# SoftCore_SA_P5.net
KiCad netlist of a schematic drawn in Altium Designer
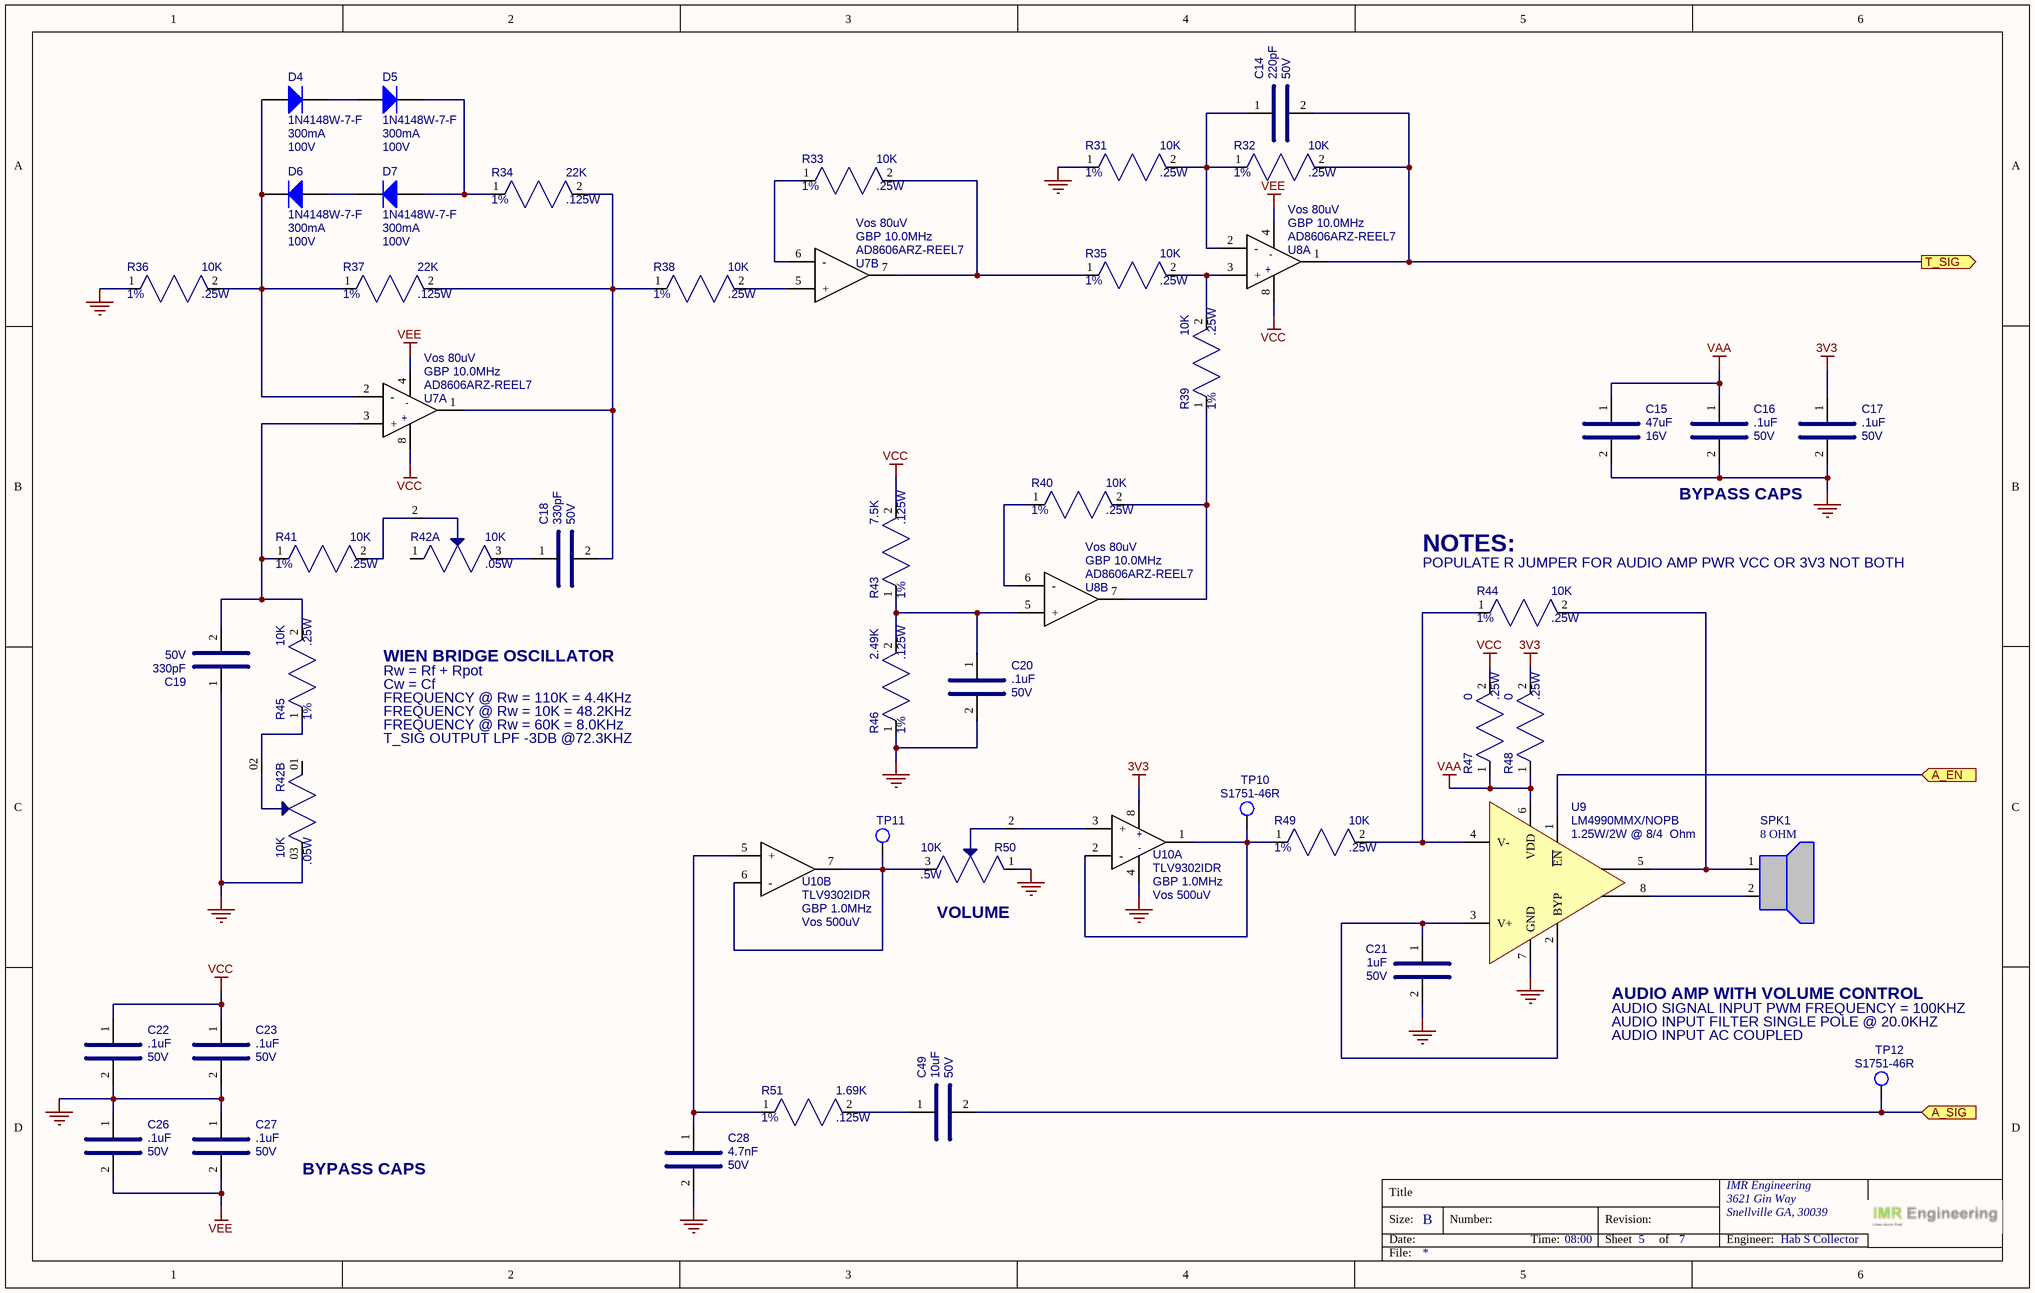
[diagram p0: SoftCore_SA_P5.SchDoc]

(export (version "E")
  (design (tool "Eeschema 10.0.6"))
  (components
    (comp (ref "C14")
      (value "220pF")
      (footprint "CAP_0805")
      (description "CAP CER 220PF 50V COG/NP0 0805")
      (fields (field (name "MFG") "Yageo") (field (name "TOLERANCE") "5%") (field (name "VOLTAGE") "50V"))
      (libsource (lib "IMR_LIB_SCH_R2") (part "CAP_SMD_220PF_50V_0805"))
    )
    (comp (ref "C15")
      (value "47uF")
      (footprint "CAP_1210")
      (description "CAP CER 47UF 50V X5R 1210")
      (fields
        (field (name "MFG") "Murata Electronics")
        (field (name "VOLTAGE") "16V")
        (field (name "Comment") "GRM32ER60J476ME20L")
      )
      (libsource (lib "IMR_LIB_SCH_R2") (part "CAP_SMD_47UF_16V_1210"))
    )
    (comp (ref "C16")
      (value ".1uF")
      (footprint "CAP_0805")
      (description "CAP CER 0.1UF 50V X7R 0805")
      (fields
        (field (name "MFG") "KYOCERA AVX")
        (field (name "VOLTAGE") "50V")
        (field (name "Comment") "KGM21NR71H104KT")
      )
      (libsource (lib "IMR_LIB_SCH_R2") (part "CAP_SMD_0.1UF_50V_0805"))
    )
    (comp (ref "C17")
      (value ".1uF")
      (footprint "CAP_0805")
      (description "CAP CER 0.1UF 50V X7R 0805")
      (fields
        (field (name "MFG") "KYOCERA AVX")
        (field (name "VOLTAGE") "50V")
        (field (name "Comment") "KGM21NR71H104KT")
      )
      (libsource (lib "IMR_LIB_SCH_R2") (part "CAP_SMD_0.1UF_50V_0805"))
    )
    (comp (ref "C18")
      (value "330pF")
      (footprint "CAP_0805")
      (description "CAP CER 3300PF 50V COG/NP0 0805")
      (fields (field (name "MFG") "Yageo") (field (name "TOLERANCE") "5%") (field (name "VOLTAGE") "50V"))
      (libsource (lib "IMR_LIB_SCH_R2") (part "CAP_SMD_330PF_50V_0805"))
    )
    (comp (ref "C19")
      (value "330pF")
      (footprint "CAP_0805")
      (description "CAP CER 3300PF 50V COG/NP0 0805")
      (fields (field (name "MFG") "Yageo") (field (name "TOLERANCE") "5%") (field (name "VOLTAGE") "50V"))
      (libsource (lib "IMR_LIB_SCH_R2") (part "CAP_SMD_330PF_50V_0805"))
    )
    (comp (ref "C20")
      (value ".1uF")
      (footprint "CAP_0805")
      (description "CAP CER 0.1UF 50V X7R 0805")
      (fields
        (field (name "MFG") "KYOCERA AVX")
        (field (name "VOLTAGE") "50V")
        (field (name "Comment") "KGM21NR71H104KT")
      )
      (libsource (lib "IMR_LIB_SCH_R2") (part "CAP_SMD_0.1UF_50V_0805"))
    )
    (comp (ref "C21")
      (value "1uF")
      (footprint "CAP_0805")
      (description "CAP CER 1UF 50V X7R 0805")
      (fields
        (field (name "MFG") "KYOCERA AVX")
        (field (name "VOLTAGE") "50V")
        (field (name "Comment") "08055C105K4T2A")
      )
      (libsource (lib "IMR_LIB_SCH_R2") (part "CAP_SMD_1UF_50V_0805"))
    )
    (comp (ref "C22")
      (value ".1uF")
      (footprint "CAP_0805")
      (description "CAP CER 0.1UF 50V X7R 0805")
      (fields
        (field (name "MFG") "KYOCERA AVX")
        (field (name "VOLTAGE") "50V")
        (field (name "Comment") "KGM21NR71H104KT")
      )
      (libsource (lib "IMR_LIB_SCH_R2") (part "CAP_SMD_0.1UF_50V_0805"))
    )
    (comp (ref "C23")
      (value ".1uF")
      (footprint "CAP_0805")
      (description "CAP CER 0.1UF 50V X7R 0805")
      (fields
        (field (name "MFG") "KYOCERA AVX")
        (field (name "VOLTAGE") "50V")
        (field (name "Comment") "KGM21NR71H104KT")
      )
      (libsource (lib "IMR_LIB_SCH_R2") (part "CAP_SMD_0.1UF_50V_0805"))
    )
    (comp (ref "C26")
      (value ".1uF")
      (footprint "CAP_0805")
      (description "CAP CER 0.1UF 50V X7R 0805")
      (fields
        (field (name "MFG") "KYOCERA AVX")
        (field (name "VOLTAGE") "50V")
        (field (name "Comment") "KGM21NR71H104KT")
      )
      (libsource (lib "IMR_LIB_SCH_R2") (part "CAP_SMD_0.1UF_50V_0805"))
    )
    (comp (ref "C27")
      (value ".1uF")
      (footprint "CAP_0805")
      (description "CAP CER 0.1UF 50V X7R 0805")
      (fields
        (field (name "MFG") "KYOCERA AVX")
        (field (name "VOLTAGE") "50V")
        (field (name "Comment") "KGM21NR71H104KT")
      )
      (libsource (lib "IMR_LIB_SCH_R2") (part "CAP_SMD_0.1UF_50V_0805"))
    )
    (comp (ref "C28")
      (value "4.7nF")
      (footprint "CAP_0805")
      (description "CAP CER 4.7NF 50V X7R 0805")
      (fields
        (field (name "MFG") "KEMET")
        (field (name "VOLTAGE") "50V")
        (field (name "Comment") "C0805C472K5RACAUTO")
      )
      (libsource (lib "IMR_LIB_SCH_R2") (part "CAP_SMD_4.7NF_50V_0805"))
    )
    (comp (ref "C49")
      (value "10uF")
      (footprint "CAP_0805")
      (description "CAP CER 10UF 50V X5R 0805")
      (fields
        (field (name "MFG") "Murata Electronics")
        (field (name "VOLTAGE") "50V")
        (field (name "Comment") "GRM21BR61H106KE43L")
      )
      (libsource (lib "IMR_LIB_SCH_R2") (part "CAP_SMD_10UF_50V_0805"))
    )
    (comp (ref "D4")
      (value "100V")
      (footprint "SOD123")
      (description "RELAY REED SPDT 250MA 5V")
      (fields
        (field (name "MFG") "Diodes Inc")
        (field (name "MFG_PN") "1N4148W-7-F")
        (field (name "CURRENT") "300mA")
        (field (name "Comment") "1N4148W-7-F")
      )
      (libsource (lib "IMR_LIB_SCH_R2") (part "DIODE_1N4148W-7-F"))
    )
    (comp (ref "D5")
      (value "100V")
      (footprint "SOD123")
      (description "RELAY REED SPDT 250MA 5V")
      (fields
        (field (name "MFG") "Diodes Inc")
        (field (name "MFG_PN") "1N4148W-7-F")
        (field (name "CURRENT") "300mA")
        (field (name "Comment") "1N4148W-7-F")
      )
      (libsource (lib "IMR_LIB_SCH_R2") (part "DIODE_1N4148W-7-F"))
    )
    (comp (ref "D6")
      (value "100V")
      (footprint "SOD123")
      (description "RELAY REED SPDT 250MA 5V")
      (fields
        (field (name "MFG") "Diodes Inc")
        (field (name "MFG_PN") "1N4148W-7-F")
        (field (name "CURRENT") "300mA")
        (field (name "Comment") "1N4148W-7-F")
      )
      (libsource (lib "IMR_LIB_SCH_R2") (part "DIODE_1N4148W-7-F"))
    )
    (comp (ref "D7")
      (value "100V")
      (footprint "SOD123")
      (description "RELAY REED SPDT 250MA 5V")
      (fields
        (field (name "MFG") "Diodes Inc")
        (field (name "MFG_PN") "1N4148W-7-F")
        (field (name "CURRENT") "300mA")
        (field (name "Comment") "1N4148W-7-F")
      )
      (libsource (lib "IMR_LIB_SCH_R2") (part "DIODE_1N4148W-7-F"))
    )
    (comp (ref "R31")
      (value "10K")
      (footprint "RES_0805")
      (description "RES SMD 10K OHM 1% 1/4W 0805")
      (fields
        (field (name "MFG") "Yageo")
        (field (name "POWER") ".25W")
        (field (name "TOLERANCE") "1%")
        (field (name "Comment") "RC0805FR-7W10KL")
      )
      (libsource (lib "IMR_LIB_SCH_R2") (part "RES_SMD_10K_0805_1/4W_1%"))
    )
    (comp (ref "R32")
      (value "10K")
      (footprint "RES_0805")
      (description "RES SMD 10K OHM 1% 1/4W 0805")
      (fields
        (field (name "MFG") "Yageo")
        (field (name "POWER") ".25W")
        (field (name "TOLERANCE") "1%")
        (field (name "Comment") "RC0805FR-7W10KL")
      )
      (libsource (lib "IMR_LIB_SCH_R2") (part "RES_SMD_10K_0805_1/4W_1%"))
    )
    (comp (ref "R33")
      (value "10K")
      (footprint "RES_0805")
      (description "RES SMD 10K OHM 1% 1/4W 0805")
      (fields
        (field (name "MFG") "Yageo")
        (field (name "POWER") ".25W")
        (field (name "TOLERANCE") "1%")
        (field (name "Comment") "RC0805FR-7W10KL")
      )
      (libsource (lib "IMR_LIB_SCH_R2") (part "RES_SMD_10K_0805_1/4W_1%"))
    )
    (comp (ref "R34")
      (value "22K")
      (footprint "RES_0805")
      (description "RES SMD 22K OHM 1% 1/8W 0805")
      (fields
        (field (name "MFG") "Yageo")
        (field (name "POWER") ".125W")
        (field (name "TOLERANCE") "1%")
        (field (name "Comment") "RC0805FR-0722KL")
      )
      (libsource (lib "IMR_LIB_SCH_R2") (part "RES_SMD_22K_0805_1/8W_1%"))
    )
    (comp (ref "R35")
      (value "10K")
      (footprint "RES_0805")
      (description "RES SMD 10K OHM 1% 1/4W 0805")
      (fields
        (field (name "MFG") "Yageo")
        (field (name "POWER") ".25W")
        (field (name "TOLERANCE") "1%")
        (field (name "Comment") "RC0805FR-7W10KL")
      )
      (libsource (lib "IMR_LIB_SCH_R2") (part "RES_SMD_10K_0805_1/4W_1%"))
    )
    (comp (ref "R36")
      (value "10K")
      (footprint "RES_0805")
      (description "RES SMD 10K OHM 1% 1/4W 0805")
      (fields
        (field (name "MFG") "Yageo")
        (field (name "POWER") ".25W")
        (field (name "TOLERANCE") "1%")
        (field (name "Comment") "RC0805FR-7W10KL")
      )
      (libsource (lib "IMR_LIB_SCH_R2") (part "RES_SMD_10K_0805_1/4W_1%"))
    )
    (comp (ref "R37")
      (value "22K")
      (footprint "RES_0805")
      (description "RES SMD 22K OHM 1% 1/8W 0805")
      (fields
        (field (name "MFG") "Yageo")
        (field (name "POWER") ".125W")
        (field (name "TOLERANCE") "1%")
        (field (name "Comment") "RC0805FR-0722KL")
      )
      (libsource (lib "IMR_LIB_SCH_R2") (part "RES_SMD_22K_0805_1/8W_1%"))
    )
    (comp (ref "R38")
      (value "10K")
      (footprint "RES_0805")
      (description "RES SMD 10K OHM 1% 1/4W 0805")
      (fields
        (field (name "MFG") "Yageo")
        (field (name "POWER") ".25W")
        (field (name "TOLERANCE") "1%")
        (field (name "Comment") "RC0805FR-7W10KL")
      )
      (libsource (lib "IMR_LIB_SCH_R2") (part "RES_SMD_10K_0805_1/4W_1%"))
    )
    (comp (ref "R39")
      (value "10K")
      (footprint "RES_0805")
      (description "RES SMD 10K OHM 1% 1/4W 0805")
      (fields
        (field (name "MFG") "Yageo")
        (field (name "POWER") ".25W")
        (field (name "TOLERANCE") "1%")
        (field (name "Comment") "RC0805FR-7W10KL")
      )
      (libsource (lib "IMR_LIB_SCH_R2") (part "RES_SMD_10K_0805_1/4W_1%"))
    )
    (comp (ref "R40")
      (value "10K")
      (footprint "RES_0805")
      (description "RES SMD 10K OHM 1% 1/4W 0805")
      (fields
        (field (name "MFG") "Yageo")
        (field (name "POWER") ".25W")
        (field (name "TOLERANCE") "1%")
        (field (name "Comment") "RC0805FR-7W10KL")
      )
      (libsource (lib "IMR_LIB_SCH_R2") (part "RES_SMD_10K_0805_1/4W_1%"))
    )
    (comp (ref "R41")
      (value "10K")
      (footprint "RES_0805")
      (description "RES SMD 10K OHM 1% 1/4W 0805")
      (fields
        (field (name "MFG") "Yageo")
        (field (name "POWER") ".25W")
        (field (name "TOLERANCE") "1%")
        (field (name "Comment") "RC0805FR-7W10KL")
      )
      (libsource (lib "IMR_LIB_SCH_R2") (part "RES_SMD_10K_0805_1/4W_1%"))
    )
    (comp (ref "R42")
      (value "10K")
      (footprint "PRS12R-4")
      (description "POT 10K OHM 1/20W LINEAR - 2X GANG")
      (fields
        (field (name "MFG") "Bourns Inc.")
        (field (name "POWER") ".05W")
        (field (name "Comment") "PRS12R-4115K-103B1")
      )
      (libsource (lib "IMR_LIB_SCH_R2") (part "RES_POT_10K_2XGANG_LINEAR"))
    )
    (comp (ref "R43")
      (value "7.5K")
      (footprint "RES_0805")
      (description "RES SMD 7.5K OHM 1% 1/8W 0805")
      (fields
        (field (name "MFG") "Yageo")
        (field (name "POWER") ".125W")
        (field (name "TOLERANCE") "1%")
        (field (name "Comment") "RC0805FR-077K5L")
      )
      (libsource (lib "IMR_LIB_SCH_R2") (part "RES_SMD_7.5K_0805_1/8W_1%"))
    )
    (comp (ref "R44")
      (value "10K")
      (footprint "RES_0805")
      (description "RES SMD 10K OHM 1% 1/4W 0805")
      (fields
        (field (name "MFG") "Yageo")
        (field (name "POWER") ".25W")
        (field (name "TOLERANCE") "1%")
        (field (name "Comment") "RC0805FR-7W10KL")
      )
      (libsource (lib "IMR_LIB_SCH_R2") (part "RES_SMD_10K_0805_1/4W_1%"))
    )
    (comp (ref "R45")
      (value "10K")
      (footprint "RES_0805")
      (description "RES SMD 10K OHM 1% 1/4W 0805")
      (fields
        (field (name "MFG") "Yageo")
        (field (name "POWER") ".25W")
        (field (name "TOLERANCE") "1%")
        (field (name "Comment") "RC0805FR-7W10KL")
      )
      (libsource (lib "IMR_LIB_SCH_R2") (part "RES_SMD_10K_0805_1/4W_1%"))
    )
    (comp (ref "R46")
      (value "2.49K")
      (footprint "RES_0805")
      (description "RES SMD 2.49K OHM 1% 1/8W 0805")
      (fields
        (field (name "MFG") "Yageo")
        (field (name "POWER") ".125W")
        (field (name "TOLERANCE") "1%")
        (field (name "Comment") "RC0805FR-132K49L")
      )
      (libsource (lib "IMR_LIB_SCH_R2") (part "RES_SMD_2.49K_0805_1/8W_1%"))
    )
    (comp (ref "R47")
      (value "0")
      (footprint "RES_0805")
      (description "RES SMD 0 OHM 1% 1/8W 0805")
      (fields (field (name "MFG") "Yageo") (field (name "TOLERANCE") "1%") (field (name "POWER") ".25W"))
      (libsource (lib "IMR_LIB_SCH_R2") (part "RES_SMD_0_0805_1/8W_1%"))
    )
    (comp (ref "R48")
      (value "0")
      (footprint "RES_0805")
      (description "RES SMD 0 OHM 1% 1/8W 0805")
      (fields (field (name "MFG") "Yageo") (field (name "TOLERANCE") "1%") (field (name "POWER") ".25W"))
      (libsource (lib "IMR_LIB_SCH_R2") (part "RES_SMD_0_0805_1/8W_1%"))
    )
    (comp (ref "R49")
      (value "10K")
      (footprint "RES_0805")
      (description "RES SMD 10K OHM 1% 1/4W 0805")
      (fields
        (field (name "MFG") "Yageo")
        (field (name "POWER") ".25W")
        (field (name "TOLERANCE") "1%")
        (field (name "Comment") "RC0805FR-7W10KL")
      )
      (libsource (lib "IMR_LIB_SCH_R2") (part "RES_SMD_10K_0805_1/4W_1%"))
    )
    (comp (ref "R50")
      (value "10K")
      (footprint "BOURNS_3386F")
      (description "POT 10K OHM 1/20W LINEAR - 1X GANG")
      (fields
        (field (name "MFG") "Bourns Inc.")
        (field (name "POWER") ".5W")
        (field (name "Comment") "3386P-1-103TLF")
      )
      (libsource (lib "IMR_LIB_SCH_R2") (part "RES_POT_10K_1XGANG_LINEAR"))
    )
    (comp (ref "R51")
      (value "1.69K")
      (footprint "RES_0805")
      (description "RES SMD 1.69K OHM 1% 1/8W 0805")
      (fields
        (field (name "MFG") "Yageo")
        (field (name "POWER") ".125W")
        (field (name "TOLERANCE") "1%")
        (field (name "Comment") "RC0805FR-071K69L")
      )
      (libsource (lib "IMR_LIB_SCH_R2") (part "RES_SMD_1.69K_0805_1/8W_1%"))
    )
    (comp (ref "SPK1")
      (value "8 OHM")
      (footprint "HDR_1X2_100MILL")
      (description "CONN SPEAKER HEADER GENERIC VERT 2POS 2.54MM")
      (fields (field (name "MFG") "GENERIC") (field (name "Comment") "TBD"))
      (libsource (lib "IMR_LIB_SCH_R2") (part "CONN_SPKR_HEADER_2P_100MIL"))
    )
    (comp (ref "TP10")
      (value "S1751-46R")
      (footprint "HARWIN_S1751")
      (description "PCB TEST POINT CONNECT")
      (fields (field (name "MFG") "Harwin Inc") (field (name "MFG_PN") "S1751-46R"))
      (libsource (lib "IMR_LIB_SCH_R2") (part "CONN_TEST_POINT_S1751-46R"))
    )
    (comp (ref "TP11")
      (value "~")
      (footprint "TEST_POINT_20MIL_TH")
      (description "TEST POINT TH 20MIL HOLE")
      (libsource (lib "IMR_LIB_SCH_R2") (part "CONN_TEST_POINT_TH_PAD_20MIL"))
    )
    (comp (ref "TP12")
      (value "S1751-46R")
      (footprint "HARWIN_S1751")
      (description "PCB TEST POINT CONNECT")
      (fields (field (name "MFG") "Harwin Inc") (field (name "MFG_PN") "S1751-46R"))
      (libsource (lib "IMR_LIB_SCH_R2") (part "CONN_TEST_POINT_S1751-46R"))
    )
    (comp (ref "U7")
      (value "GBP 10.0MHz")
      (footprint "SOIC-8_54")
      (description "IC OPAMP GP 2 CIRCUIT 8SOIC")
      (fields
        (field (name "MFG") "Analog Devices")
        (field (name "MFG_PN") "AD8606ARZ-REEL7")
        (field (name "VOS") "Vos 80uV")
        (field (name "Comment") "AD8606ARZ-REEL7")
      )
      (libsource (lib "IMR_LIB_SCH_R2") (part "IC_OPAMP_AD8606ARZ-REEL7"))
    )
    (comp (ref "U8")
      (value "GBP 10.0MHz")
      (footprint "SOIC-8_54")
      (description "IC OPAMP GP 2 CIRCUIT 8SOIC")
      (fields
        (field (name "MFG") "Analog Devices")
        (field (name "MFG_PN") "AD8606ARZ-REEL7")
        (field (name "VOS") "Vos 80uV")
        (field (name "Comment") "AD8606ARZ-REEL7")
      )
      (libsource (lib "IMR_LIB_SCH_R2") (part "IC_OPAMP_AD8606ARZ-REEL7"))
    )
    (comp (ref "U9")
      (value "1.25W/2W @ 8/4  Ohm")
      (footprint "SOP65P490X110-8N")
      (description "IC AMP CLASS AB MONO 2W 8VSSOP")
      (fields
        (field (name "MFG") "Texas Instruments")
        (field (name "MFG_PN") "LM4990MMX/NOPB")
        (field (name "Comment") "LM4990MMX/NOPB")
      )
      (libsource (lib "IMR_LIB_SCH_R2") (part "IC_LM4990MMX/NOPB"))
    )
    (comp (ref "U10")
      (value "GBP 1.0MHz")
      (footprint "SOIC-8_49")
      (description "IC OPAMP GP 2 CIRCUIT 8SOIC")
      (fields
        (field (name "MFG") "Texas Instruments")
        (field (name "MFG_PN") "TLV9302IDR")
        (field (name "VOS") "Vos 500uV")
        (field (name "Comment") "TLV9302IDR")
      )
      (libsource (lib "IMR_LIB_SCH_R2") (part "IC_OPAMP_TLV9302IDR"))
    )
  )
  (nets
    (net (code "1") (name "/A_EN") (class "Default")
      (node (ref "U9") (pin "1") (pinfunction "EN_1") (pintype "passive"))
    )
    (net (code "2") (name "/A_SIG") (class "Default")
      (node (ref "C49") (pin "2") (pinfunction "2_2") (pintype "passive"))
      (node (ref "TP12") (pin "1") (pintype "passive"))
    )
    (net (code "3") (name "/T_SIG") (class "Default")
      (node (ref "C14") (pin "2") (pinfunction "2_2") (pintype "passive"))
      (node (ref "R32") (pin "2") (pinfunction "2_2") (pintype "passive"))
      (node (ref "U8") (pin "1") (pintype "passive"))
    )
    (net (code "4") (name "3V3") (class "Default")
      (node (ref "C17") (pin "1") (pinfunction "1_1") (pintype "passive"))
      (node (ref "R48") (pin "2") (pinfunction "2_2") (pintype "passive"))
      (node (ref "U10") (pin "8") (pintype "passive"))
    )
    (net (code "5") (name "GND") (class "Default")
      (node (ref "C15") (pin "2") (pinfunction "2_2") (pintype "passive"))
      (node (ref "C16") (pin "2") (pinfunction "2_2") (pintype "passive"))
      (node (ref "C17") (pin "2") (pinfunction "2_2") (pintype "passive"))
      (node (ref "C19") (pin "1") (pinfunction "1_1") (pintype "passive"))
      (node (ref "C20") (pin "2") (pinfunction "2_2") (pintype "passive"))
      (node (ref "C21") (pin "2") (pinfunction "2_2") (pintype "passive"))
      (node (ref "C22") (pin "2") (pinfunction "2_2") (pintype "passive"))
      (node (ref "C23") (pin "2") (pinfunction "2_2") (pintype "passive"))
      (node (ref "C26") (pin "1") (pinfunction "1_1") (pintype "passive"))
      (node (ref "C27") (pin "1") (pinfunction "1_1") (pintype "passive"))
      (node (ref "C28") (pin "2") (pinfunction "2_2") (pintype "passive"))
      (node (ref "R31") (pin "1") (pinfunction "1_1") (pintype "passive"))
      (node (ref "R36") (pin "1") (pinfunction "1_1") (pintype "passive"))
      (node (ref "R42") (pin "03") (pinfunction "3_03") (pintype "passive"))
      (node (ref "R46") (pin "1") (pinfunction "1_1") (pintype "passive"))
      (node (ref "R50") (pin "1") (pinfunction "1_1") (pintype "passive"))
      (node (ref "U10") (pin "4") (pintype "passive"))
      (node (ref "U9") (pin "7") (pinfunction "GND_7") (pintype "passive"))
    )
    (net (code "6") (name "Net-(C18-Pad1)") (class "Default")
      (node (ref "C18") (pin "1") (pinfunction "1_1") (pintype "passive"))
      (node (ref "R42") (pin "3") (pinfunction "3_3") (pintype "passive"))
    )
    (net (code "7") (name "Net-(C18-Pad2)") (class "Default")
      (node (ref "C18") (pin "2") (pinfunction "2_2") (pintype "passive"))
      (node (ref "R34") (pin "2") (pinfunction "2_2") (pintype "passive"))
      (node (ref "R37") (pin "2") (pinfunction "2_2") (pintype "passive"))
      (node (ref "R38") (pin "1") (pinfunction "1_1") (pintype "passive"))
      (node (ref "U7") (pin "1") (pintype "passive"))
    )
    (net (code "8") (name "Net-(C49-Pad1)") (class "Default")
      (node (ref "C49") (pin "1") (pinfunction "1_1") (pintype "passive"))
      (node (ref "R51") (pin "2") (pinfunction "2_2") (pintype "passive"))
    )
    (net (code "9") (name "Net-(D4-A)") (class "Default")
      (node (ref "D4") (pin "1") (pinfunction "A_1") (pintype "passive"))
      (node (ref "D6") (pin "2") (pinfunction "K_2") (pintype "passive"))
      (node (ref "R36") (pin "2") (pinfunction "2_2") (pintype "passive"))
      (node (ref "R37") (pin "1") (pinfunction "1_1") (pintype "passive"))
      (node (ref "U7") (pin "2") (pinfunction "-_2") (pintype "passive"))
    )
    (net (code "10") (name "Net-(D4-K)") (class "Default")
      (node (ref "D4") (pin "2") (pinfunction "K_2") (pintype "passive"))
      (node (ref "D5") (pin "1") (pinfunction "A_1") (pintype "passive"))
    )
    (net (code "11") (name "Net-(D5-K)") (class "Default")
      (node (ref "D5") (pin "2") (pinfunction "K_2") (pintype "passive"))
      (node (ref "D7") (pin "1") (pinfunction "A_1") (pintype "passive"))
      (node (ref "R34") (pin "1") (pinfunction "1_1") (pintype "passive"))
    )
    (net (code "12") (name "Net-(D6-A)") (class "Default")
      (node (ref "D6") (pin "1") (pinfunction "A_1") (pintype "passive"))
      (node (ref "D7") (pin "2") (pinfunction "K_2") (pintype "passive"))
    )
    (net (code "13") (name "Net-(R33-Pad2)") (class "Default")
      (node (ref "R33") (pin "2") (pinfunction "2_2") (pintype "passive"))
      (node (ref "R35") (pin "1") (pinfunction "1_1") (pintype "passive"))
      (node (ref "U7") (pin "7") (pintype "passive"))
    )
    (net (code "14") (name "Net-(R39-Pad1)") (class "Default")
      (node (ref "R39") (pin "1") (pinfunction "1_1") (pintype "passive"))
      (node (ref "R40") (pin "2") (pinfunction "2_2") (pintype "passive"))
      (node (ref "U8") (pin "7") (pintype "passive"))
    )
    (net (code "15") (name "Net-(R41-Pad2)") (class "Default")
      (node (ref "R41") (pin "2") (pinfunction "2_2") (pintype "passive"))
      (node (ref "R42") (pin "2") (pinfunction "2_2") (pintype "passive"))
    )
    (net (code "16") (name "Net-(R42-Pad02)") (class "Default")
      (node (ref "R42") (pin "02") (pinfunction "02_02") (pintype "passive"))
      (node (ref "R45") (pin "1") (pinfunction "1_1") (pintype "passive"))
    )
    (net (code "17") (name "Net-(U7A-+)") (class "Default")
      (node (ref "C19") (pin "2") (pinfunction "2_2") (pintype "passive"))
      (node (ref "R41") (pin "1") (pinfunction "1_1") (pintype "passive"))
      (node (ref "R45") (pin "2") (pinfunction "2_2") (pintype "passive"))
      (node (ref "U7") (pin "3") (pinfunction "+_3") (pintype "passive"))
    )
    (net (code "18") (name "Net-(U7B-+)") (class "Default")
      (node (ref "R38") (pin "2") (pinfunction "2_2") (pintype "passive"))
      (node (ref "U7") (pin "5") (pinfunction "+_5") (pintype "passive"))
    )
    (net (code "19") (name "Net-(U7B--)") (class "Default")
      (node (ref "R33") (pin "1") (pinfunction "1_1") (pintype "passive"))
      (node (ref "U7") (pin "6") (pinfunction "-_6") (pintype "passive"))
    )
    (net (code "20") (name "Net-(U8A-+)") (class "Default")
      (node (ref "R35") (pin "2") (pinfunction "2_2") (pintype "passive"))
      (node (ref "R39") (pin "2") (pinfunction "2_2") (pintype "passive"))
      (node (ref "U8") (pin "3") (pinfunction "+_3") (pintype "passive"))
    )
    (net (code "21") (name "Net-(U8A--)") (class "Default")
      (node (ref "C14") (pin "1") (pinfunction "1_1") (pintype "passive"))
      (node (ref "R31") (pin "2") (pinfunction "2_2") (pintype "passive"))
      (node (ref "R32") (pin "1") (pinfunction "1_1") (pintype "passive"))
      (node (ref "U8") (pin "2") (pinfunction "-_2") (pintype "passive"))
    )
    (net (code "22") (name "Net-(U8B-+)") (class "Default")
      (node (ref "C20") (pin "1") (pinfunction "1_1") (pintype "passive"))
      (node (ref "R43") (pin "1") (pinfunction "1_1") (pintype "passive"))
      (node (ref "R46") (pin "2") (pinfunction "2_2") (pintype "passive"))
      (node (ref "U8") (pin "5") (pinfunction "+_5") (pintype "passive"))
    )
    (net (code "23") (name "Net-(U8B--)") (class "Default")
      (node (ref "R40") (pin "1") (pinfunction "1_1") (pintype "passive"))
      (node (ref "U8") (pin "6") (pinfunction "-_6") (pintype "passive"))
    )
    (net (code "24") (name "Net-(U9-BYP)") (class "Default")
      (node (ref "C21") (pin "1") (pinfunction "1_1") (pintype "passive"))
      (node (ref "U9") (pin "2") (pinfunction "BYP_2") (pintype "passive"))
      (node (ref "U9") (pin "3") (pinfunction "V+_3") (pintype "passive"))
    )
    (net (code "25") (name "Net-(U9-V-)") (class "Default")
      (node (ref "R44") (pin "1") (pinfunction "1_1") (pintype "passive"))
      (node (ref "R49") (pin "2") (pinfunction "2_2") (pintype "passive"))
      (node (ref "U9") (pin "4") (pinfunction "V-_4") (pintype "passive"))
    )
    (net (code "26") (name "Net-(U9-VO1)") (class "Default")
      (node (ref "R44") (pin "2") (pinfunction "2_2") (pintype "passive"))
      (node (ref "SPK1") (pin "1") (pintype "passive"))
      (node (ref "U9") (pin "5") (pinfunction "VO1_5") (pintype "passive"))
    )
    (net (code "27") (name "Net-(U9-VO2)") (class "Default")
      (node (ref "SPK1") (pin "2") (pintype "passive"))
      (node (ref "U9") (pin "8") (pinfunction "VO2_8") (pintype "passive"))
    )
    (net (code "28") (name "Net-(U10A-+)") (class "Default")
      (node (ref "R50") (pin "2") (pinfunction "2_2") (pintype "passive"))
      (node (ref "U10") (pin "3") (pinfunction "+_3") (pintype "passive"))
    )
    (net (code "29") (name "Net-(U10A--)") (class "Default")
      (node (ref "R49") (pin "1") (pinfunction "1_1") (pintype "passive"))
      (node (ref "TP10") (pin "1") (pintype "passive"))
      (node (ref "U10") (pin "1") (pintype "passive"))
      (node (ref "U10") (pin "2") (pinfunction "-_2") (pintype "passive"))
    )
    (net (code "30") (name "Net-(U10B-+)") (class "Default")
      (node (ref "C28") (pin "1") (pinfunction "1_1") (pintype "passive"))
      (node (ref "R51") (pin "1") (pinfunction "1_1") (pintype "passive"))
      (node (ref "U10") (pin "5") (pinfunction "+_5") (pintype "passive"))
    )
    (net (code "31") (name "Net-(U10B--)") (class "Default")
      (node (ref "R50") (pin "3") (pinfunction "3_3") (pintype "passive"))
      (node (ref "TP11") (pin "1") (pintype "passive"))
      (node (ref "U10") (pin "6") (pinfunction "-_6") (pintype "passive"))
      (node (ref "U10") (pin "7") (pintype "passive"))
    )
    (net (code "32") (name "VAA") (class "Default")
      (node (ref "C15") (pin "1") (pinfunction "1_1") (pintype "passive"))
      (node (ref "C16") (pin "1") (pinfunction "1_1") (pintype "passive"))
      (node (ref "R47") (pin "1") (pinfunction "1_1") (pintype "passive"))
      (node (ref "R48") (pin "1") (pinfunction "1_1") (pintype "passive"))
      (node (ref "U9") (pin "6") (pinfunction "VDD_6") (pintype "passive"))
    )
    (net (code "33") (name "VCC") (class "Default")
      (node (ref "C22") (pin "1") (pinfunction "1_1") (pintype "passive"))
      (node (ref "C23") (pin "1") (pinfunction "1_1") (pintype "passive"))
      (node (ref "R43") (pin "2") (pinfunction "2_2") (pintype "passive"))
      (node (ref "R47") (pin "2") (pinfunction "2_2") (pintype "passive"))
      (node (ref "U7") (pin "8") (pintype "passive"))
      (node (ref "U8") (pin "8") (pintype "passive"))
    )
    (net (code "34") (name "VEE") (class "Default")
      (node (ref "C26") (pin "2") (pinfunction "2_2") (pintype "passive"))
      (node (ref "C27") (pin "2") (pinfunction "2_2") (pintype "passive"))
      (node (ref "U7") (pin "4") (pintype "passive"))
      (node (ref "U8") (pin "4") (pintype "passive"))
    )
    (net (code "35") (name "unconnected-(R42-Pad01)") (class "Default")
      (node (ref "R42") (pin "01") (pinfunction "01_01") (pintype "passive"))
    )
    (net (code "36") (name "unconnected-(R42-Pad1)") (class "Default")
      (node (ref "R42") (pin "1") (pinfunction "1_1") (pintype "passive"))
    )
  )
)
